# Dynamixel_Servos_AXRX.net
KiCad netlist of a schematic drawn in Altium Designer
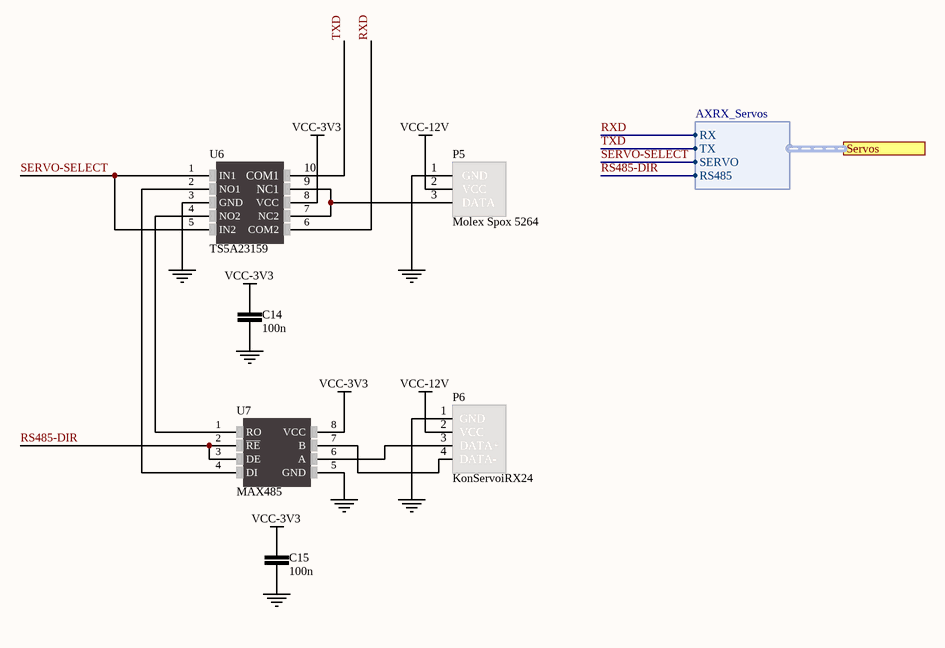
[diagram p0: Dynamixel_Servos_AXRX.SchDoc]

(export (version "E")
  (design (tool "Eeschema 10.0.6"))
  (components
    (comp (ref "C14")
      (value "100n")
      (footprint "CER_0603")
      (description "CAP CER 100n 10V X5R 10% 0603")
      (libsource (lib "Capacitors") (part "06032105"))
    )
    (comp (ref "C15")
      (value "100n")
      (footprint "CER_0603")
      (description "CAP CER 100n 10V X5R 10% 0603")
      (libsource (lib "Capacitors") (part "06032105"))
    )
    (comp (ref "P5")
      (value "Molex Spox 5264")
      (footprint "AX12_Molex Spox 5264")
      (description "KonServoiAX12")
      (fields (field (name "MANUFACTURER") "Molex"))
      (libsource (lib "Electro_Mechanical") (part "AX12_CONECTOR"))
    )
    (comp (ref "P6")
      (value "KonServoiRX24")
      (footprint "RX24_Molex Spox 5264")
      (description "Molex Spox 5264")
      (fields (field (name "MANUFACTURER") "Molex"))
      (libsource (lib "Electro_Mechanical") (part "RX24_CONECTOR"))
    )
    (comp (ref "U6")
      (value "TS5A23159")
      (footprint "TSSOP10")
      (description "IC SWITCH DUAL SPDT 10MSOP")
      (libsource (lib "Integrated_circuits") (part "00000008_1"))
    )
    (comp (ref "U7")
      (value "MAX485")
      (footprint "SOIC-8")
      (description "IC TXRX RS485/RS422 8-SOIC")
      (libsource (lib "Integrated_circuits") (part "00000008"))
    )
  )
  (nets
    (net (code "2") (name "/RS485-DIR") (class "Default")
      (node (ref "U7") (pin "2") (pinfunction "~{RE}_2") (pintype "passive"))
      (node (ref "U7") (pin "3") (pinfunction "DE_3") (pintype "passive"))
    )
    (net (code "3") (name "/RXD") (class "Default")
      (node (ref "U6") (pin "6") (pinfunction "COM2_6") (pintype "passive"))
    )
    (net (code "4") (name "/SERVO-SELECT") (class "Default")
      (node (ref "U6") (pin "1") (pinfunction "IN1_1") (pintype "passive"))
      (node (ref "U6") (pin "5") (pinfunction "IN2_5") (pintype "passive"))
    )
    (net (code "5") (name "/TXD") (class "Default")
      (node (ref "U6") (pin "10") (pinfunction "COM1_10") (pintype "passive"))
    )
    (net (code "7") (name "GND") (class "Default")
      (node (ref "C14") (pin "1") (pinfunction "1_1") (pintype "passive"))
      (node (ref "C15") (pin "1") (pinfunction "1_1") (pintype "passive"))
      (node (ref "P5") (pin "1") (pinfunction "GND_1") (pintype "passive"))
      (node (ref "P6") (pin "1") (pinfunction "GND_1") (pintype "passive"))
      (node (ref "U6") (pin "3") (pinfunction "GND_3") (pintype "passive"))
      (node (ref "U7") (pin "5") (pinfunction "GND_5") (pintype "passive"))
    )
    (net (code "8") (name "Net-(P5-DATA)") (class "Default")
      (node (ref "P5") (pin "3") (pinfunction "DATA_3") (pintype "passive"))
      (node (ref "U6") (pin "7") (pinfunction "NC2_7") (pintype "passive"))
      (node (ref "U6") (pin "9") (pinfunction "NC1_9") (pintype "passive"))
    )
    (net (code "9") (name "Net-(P6-DATA+)") (class "Default")
      (node (ref "P6") (pin "3") (pinfunction "DATA+_3") (pintype "passive"))
      (node (ref "U7") (pin "6") (pinfunction "A_6") (pintype "passive"))
    )
    (net (code "10") (name "Net-(P6-DATA-)") (class "Default")
      (node (ref "P6") (pin "4") (pinfunction "DATA-_4") (pintype "passive"))
      (node (ref "U7") (pin "7") (pinfunction "B_7") (pintype "passive"))
    )
    (net (code "11") (name "Net-(U6-NO1)") (class "Default")
      (node (ref "U6") (pin "2") (pinfunction "NO1_2") (pintype "passive"))
      (node (ref "U7") (pin "4") (pinfunction "DI_4") (pintype "passive"))
    )
    (net (code "12") (name "Net-(U6-NO2)") (class "Default")
      (node (ref "U6") (pin "4") (pinfunction "NO2_4") (pintype "passive"))
      (node (ref "U7") (pin "1") (pinfunction "RO_1") (pintype "passive"))
    )
    (net (code "13") (name "VCC-3V3") (class "Default")
      (node (ref "C14") (pin "2") (pinfunction "2_2") (pintype "passive"))
      (node (ref "C15") (pin "2") (pinfunction "2_2") (pintype "passive"))
      (node (ref "U6") (pin "8") (pinfunction "VCC_8") (pintype "passive"))
      (node (ref "U7") (pin "8") (pinfunction "VCC_8") (pintype "passive"))
    )
    (net (code "14") (name "VCC-12V") (class "Default")
      (node (ref "P5") (pin "2") (pinfunction "VCC_2") (pintype "passive"))
      (node (ref "P6") (pin "2") (pinfunction "VCC_2") (pintype "passive"))
    )
  )
)
